# Charger_Interface_-_J1772_Interface.net
KiCad netlist of a schematic drawn in Altium Designer
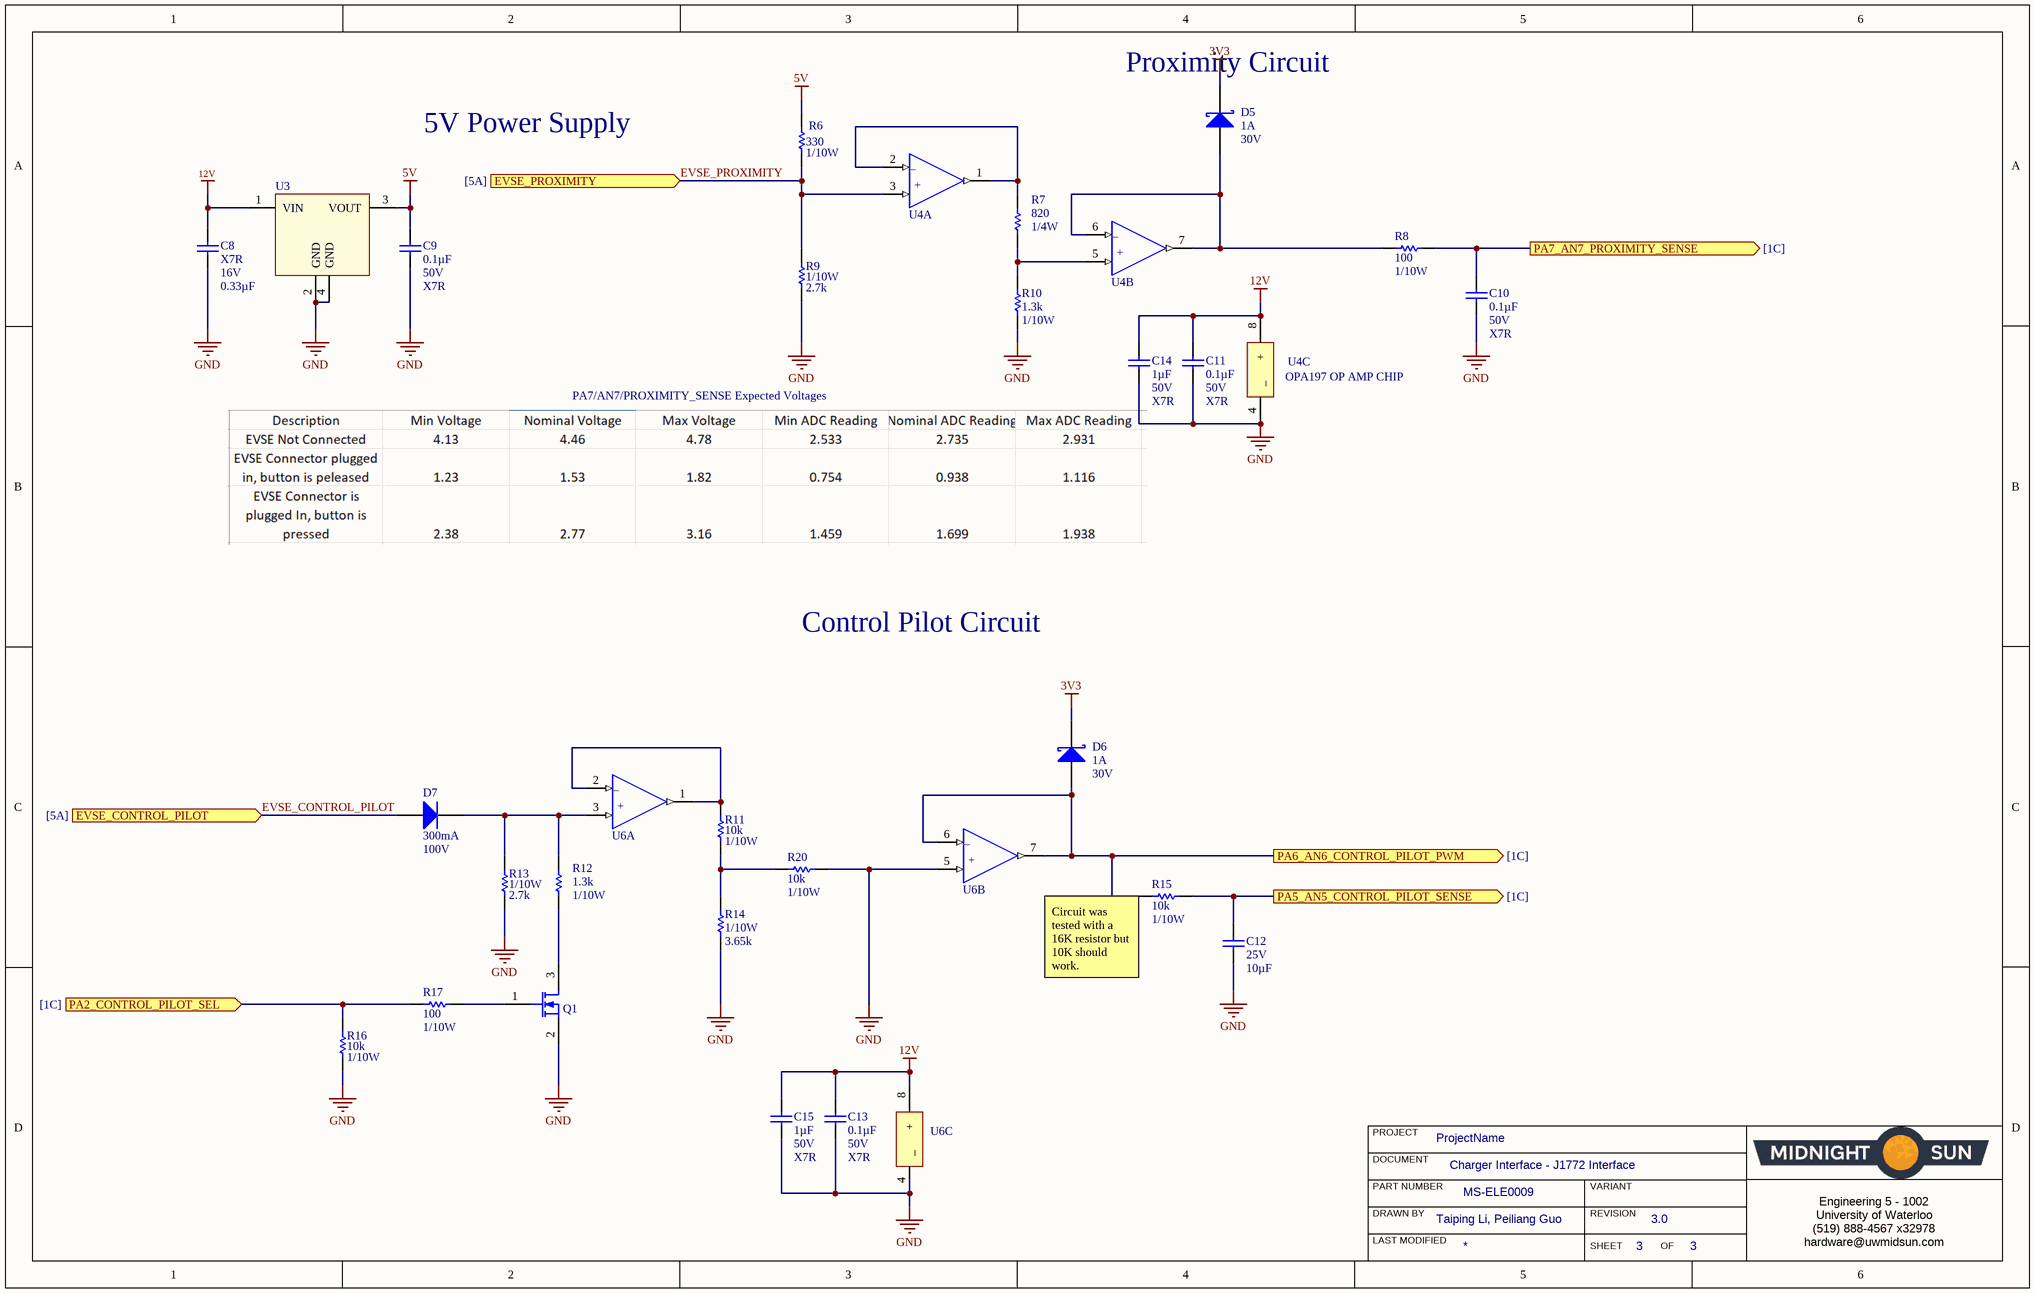
[diagram p0: Charger Interface - J1772 Interface.SchDoc]

(export (version "E")
  (design (tool "Eeschema 10.0.6"))
  (components
    (comp (ref "C8")
      (value "CAP CER 0.33UF 16V 10% X7R 0603")
      (footprint "CAP, 0603")
      (description "0.33µF ±10% 16V Ceramic Capacitor X7R 0603 (1608 Metric)")
      (fields
        (field (name "MANUFACTURER") "KEMET")
        (field (name "MANUFACTURER PART NUMBER") "C0603C334K4RACTU")
        (field (name "DIELECTRIC") "X7R")
        (field (name "VOLTAGE") "16V")
        (field (name "CAPACITANCE") "0.33µF")
      )
      (libsource (lib "Schematic Diagrams") (part "CAP CER 0.33UF 16V 10% X7R 0603"))
    )
    (comp (ref "C9")
      (value "CAP CER 0.1UF 50V 10% X7R 0603")
      (footprint "CAP, 0603")
      (description "0.10µF ±10% 50V Ceramic Capacitor X7R 0603 (1608 Metric)")
      (fields
        (field (name "TOLERANCE") "±10%")
        (field (name "CAPACITANCE") "0.1µF")
        (field (name "VOLTAGE") "50V")
        (field (name "TEMPERATURE COEFFICIENT") "X7R")
      )
      (libsource (lib "Schematic Diagrams") (part "CAP CER 0.1UF 50V 10% X7R 0603"))
    )
    (comp (ref "C10")
      (value "CAP CER 0.1UF 50V 10% X7R 0603")
      (footprint "CAP, 0603")
      (description "0.10µF ±10% 50V Ceramic Capacitor X7R 0603 (1608 Metric)")
      (fields
        (field (name "TOLERANCE") "±10%")
        (field (name "CAPACITANCE") "0.1µF")
        (field (name "VOLTAGE") "50V")
        (field (name "TEMPERATURE COEFFICIENT") "X7R")
      )
      (libsource (lib "Schematic Diagrams") (part "CAP CER 0.1UF 50V 10% X7R 0603"))
    )
    (comp (ref "C11")
      (value "CAP CER 0.1UF 50V 10% X7R 0603")
      (footprint "CAP, 0603")
      (description "0.10µF ±10% 50V Ceramic Capacitor X7R 0603 (1608 Metric)")
      (fields
        (field (name "TOLERANCE") "±10%")
        (field (name "CAPACITANCE") "0.1µF")
        (field (name "VOLTAGE") "50V")
        (field (name "TEMPERATURE COEFFICIENT") "X7R")
      )
      (libsource (lib "Schematic Diagrams") (part "CAP CER 0.1UF 50V 10% X7R 0603"))
    )
    (comp (ref "C12")
      (value "CAP CER 10uF 25V 10% X5R 0805")
      (footprint "CAP, 0805")
      (description "10µF ±10% 25V Ceramic Capacitor X5R 0805 (2012 Metric)")
      (fields
        (field (name "MANUFACTURER") "Murata Electronics North America")
        (field (name "MANUFACTURER PART NUMBER") "GRM21BR61E106KA73L")
        (field (name "VOLTAGE - RATED") "25V")
        (field (name "CAPACITANCE") "10µF")
      )
      (libsource (lib "Schematic Diagrams") (part "CAP CER 10uF 25V 10% X5R 0805"))
    )
    (comp (ref "C13")
      (value "CAP CER 0.1UF 50V 10% X7R 0603")
      (footprint "CAP, 0603")
      (description "0.10µF ±10% 50V Ceramic Capacitor X7R 0603 (1608 Metric)")
      (fields
        (field (name "TOLERANCE") "±10%")
        (field (name "CAPACITANCE") "0.1µF")
        (field (name "VOLTAGE") "50V")
        (field (name "TEMPERATURE COEFFICIENT") "X7R")
      )
      (libsource (lib "Schematic Diagrams") (part "CAP CER 0.1UF 50V 10% X7R 0603"))
    )
    (comp (ref "C14")
      (value "CAP CER 1UF 50V 10% X7R 0603")
      (footprint "CAP, 0603")
      (description "1µF ±10% 50V Ceramic Capacitor X7R 0603 (1608 Metric)")
      (fields
        (field (name "TOLERANCE") "±10%")
        (field (name "CAPACITANCE") "1µF")
        (field (name "VOLTAGE") "50V")
        (field (name "TEMPERATURE COEFFICIENT") "X7R")
      )
      (libsource (lib "Schematic Diagrams") (part "CAP CER 1UF 50V 10% X7R 0603"))
    )
    (comp (ref "C15")
      (value "CAP CER 1UF 50V 10% X7R 0603")
      (footprint "CAP, 0603")
      (description "1µF ±10% 50V Ceramic Capacitor X7R 0603 (1608 Metric)")
      (fields
        (field (name "TOLERANCE") "±10%")
        (field (name "CAPACITANCE") "1µF")
        (field (name "VOLTAGE") "50V")
        (field (name "TEMPERATURE COEFFICIENT") "X7R")
      )
      (libsource (lib "Schematic Diagrams") (part "CAP CER 1UF 50V 10% X7R 0603"))
    )
    (comp (ref "D5")
      (value "DIODE SCHOTTKY 30V 1A POWERDI123")
      (footprint "DIODE SCHOTTKY 30V 1A POWERDI123")
      (description "Diode Schottky 30V 1A Surface Mount PowerDI™ 123")
      (fields
        (field (name "MANUFACTURER") "Diodes Incorporated")
        (field (name "MANUFACTURER PART NUMBER") "DFLS130L-7")
        (field (name "CURRENT - AVERAGE RECTIFIED (IO)") "1A")
        (field (name "VOLTAGE - DC REVERSE (VR) (MAX)") "30V")
      )
      (libsource (lib "Schematic Diagrams") (part "DIODE SCHOTTKY 30V 1A POWERDI123"))
    )
    (comp (ref "D6")
      (value "DIODE SCHOTTKY 30V 1A POWERDI123")
      (footprint "DIODE SCHOTTKY 30V 1A POWERDI123")
      (description "Diode Schottky 30V 1A Surface Mount PowerDI™ 123")
      (fields
        (field (name "MANUFACTURER") "Diodes Incorporated")
        (field (name "MANUFACTURER PART NUMBER") "DFLS130L-7")
        (field (name "CURRENT - AVERAGE RECTIFIED (IO)") "1A")
        (field (name "VOLTAGE - DC REVERSE (VR) (MAX)") "30V")
      )
      (libsource (lib "Schematic Diagrams") (part "DIODE SCHOTTKY 30V 1A POWERDI123"))
    )
    (comp (ref "D7")
      (value "DIODE GEN PURP 100V 300MA SOD123")
      (footprint "DIODE GEN PURP 100V 300MA SOD123")
      (description "Diode Standard 100V 300mA (DC) Surface Mount SOD-123")
      (fields
        (field (name "MANUFACTURER") "Diodes Zetex")
        (field (name "MANUFACTURER PART NUMBER") "1N4148WQ-7-F")
        (field (name "FORWARD CURRENT") "300mA")
        (field (name "MAX REPETITIVE REVERSE VOLTAGE (VRRM)") "100V")
      )
      (libsource (lib "Schematic Diagrams") (part "DIODE GEN PURP 100V 300MA SOD123"))
    )
    (comp (ref "Q1")
      (value "MOSFET N-CH 30V 6.2A 0.9W SOT-23")
      (footprint "MOSFET N-CH 30V 6.2A 0.9W SOT-23")
      (description "N-Channel 30V 6.2A (Ta) 900mW (Ta) Surface Mount SOT-23")
      (fields (field (name "MANUFACTURER") "Diodes") (field (name "MANUFACTURER PART NUMBER") "DMN3023L-7"))
      (libsource (lib "Schematic Diagrams") (part "MOSFET N-CH 30V 6.2A 0.9W SOT-23"))
    )
    (comp (ref "R6")
      (value "RES 330 OHM 1% 1/10W 0603")
      (footprint "RES, 0603")
      (fields
        (field (name "MANUFACTURER") "TE Connectivity")
        (field (name "MANUFACTURER PART NUMBER") "1-2176339-9")
        (field (name "RESISTANCE") "330")
        (field (name "POWER") "1/10W")
      )
      (libsource (lib "Schematic Diagrams") (part "RES 330 OHM 1% 1/10W 0603"))
    )
    (comp (ref "R7")
      (value "RES 820 OHM 5% 1/4W 0603")
      (footprint "RES, 0603")
      (description "RES SMD 820 OHM 5% 1/4W 0603")
      (fields
        (field (name "TOLERANCE") "±5%")
        (field (name "RESISTANCE") "820")
        (field (name "POWER") "1/4W")
      )
      (libsource (lib "Schematic Diagrams") (part "RES 820 OHM 5% 1/4W 0603"))
    )
    (comp (ref "R8")
      (value "RES 100 OHM 1% 1/10W 0603")
      (footprint "RES, 0603")
      (description "100 Ohm ±1% 0.1W, 1/10W Chip Resistor 0603 (1608 Metric) Moisture Resistant Thick Film")
      (fields
        (field (name "TOLERANCE") "±1%")
        (field (name "RESISTANCE") "100")
        (field (name "POWER") "1/10W")
      )
      (libsource (lib "Schematic Diagrams") (part "RES 100 OHM 1% 1/10W 0603"))
    )
    (comp (ref "R9")
      (value "RES 2.7K OHM 1% 1/10W 0603")
      (footprint "RES, 0603")
      (fields
        (field (name "MANUFACTURER") "TE Connectivity")
        (field (name "MANUFACTURER PART NUMBER") "3-2176339-0")
        (field (name "POWER") "1/10W")
        (field (name "RESISTANCE") "2.7k")
      )
      (libsource (lib "Schematic Diagrams") (part "RES 2.7K OHM 1% 1/10W 0603"))
    )
    (comp (ref "R10")
      (value "RES 1.3K OHM 1% 1/10W 0603")
      (footprint "RES, 0603")
      (description "1.3 kOhms ±1% 0.1W, 1/10W Chip Resistor 0603 (1608 Metric) Moisture Resistant Thick Film")
      (fields
        (field (name "MANUFACTURER") "Yageo")
        (field (name "MANUFACTURER PART NUMBER") "RC0603FR-071K3L")
        (field (name "RESISTANCE") "1.3k")
        (field (name "POWER RATING") "1/10W")
      )
      (libsource (lib "Schematic Diagrams") (part "RES 1.3K OHM 1% 1/10W 0603"))
    )
    (comp (ref "R11")
      (value "RES 10K OHM 1% 1/10W 0603")
      (footprint "RES, 0603")
      (description "RES SMD 10K OHM 1% 1/10W 0603")
      (fields
        (field (name "TOLERANCE") "±1%")
        (field (name "RESISTANCE") "10k")
        (field (name "POWER") "1/10W")
      )
      (libsource (lib "Schematic Diagrams") (part "RES 10K OHM 1% 1/10W 0603"))
    )
    (comp (ref "R12")
      (value "RES 1.3K OHM 1% 1/10W 0603")
      (footprint "RES, 0603")
      (description "1.3 kOhms ±1% 0.1W, 1/10W Chip Resistor 0603 (1608 Metric) Moisture Resistant Thick Film")
      (fields
        (field (name "MANUFACTURER") "Yageo")
        (field (name "MANUFACTURER PART NUMBER") "RC0603FR-071K3L")
        (field (name "RESISTANCE") "1.3k")
        (field (name "POWER RATING") "1/10W")
      )
      (libsource (lib "Schematic Diagrams") (part "RES 1.3K OHM 1% 1/10W 0603"))
    )
    (comp (ref "R13")
      (value "RES 2.7K OHM 1% 1/10W 0603")
      (footprint "RES, 0603")
      (fields
        (field (name "MANUFACTURER") "TE Connectivity")
        (field (name "MANUFACTURER PART NUMBER") "3-2176339-0")
        (field (name "POWER") "1/10W")
        (field (name "RESISTANCE") "2.7k")
      )
      (libsource (lib "Schematic Diagrams") (part "RES 2.7K OHM 1% 1/10W 0603"))
    )
    (comp (ref "R14")
      (value "RES 3.65K OHM 0.1% 1/10W 0603")
      (footprint "RES, 0603")
      (description "3.65 kOhms ±0.1% 0.1W, 1/10W Chip Resistor 0603 (1608 Metric) Automotive AEC-Q200 Thin Film")
      (fields
        (field (name "MANUFACTURER") "Panasonic")
        (field (name "MANUFACTURER PART NUMBER") "ERA3AEB3651V")
        (field (name "POWER RATING") "1/10W")
        (field (name "RESISTANCE") "3.65k")
      )
      (libsource (lib "Schematic Diagrams") (part "RES 3.65K OHM 0.1% 1/10W 0603"))
    )
    (comp (ref "R15")
      (value "RES 10K OHM 1% 1/10W 0603")
      (footprint "RES, 0603")
      (description "RES SMD 10K OHM 1% 1/10W 0603")
      (fields
        (field (name "TOLERANCE") "±1%")
        (field (name "RESISTANCE") "10k")
        (field (name "POWER") "1/10W")
      )
      (libsource (lib "Schematic Diagrams") (part "RES 10K OHM 1% 1/10W 0603"))
    )
    (comp (ref "R16")
      (value "RES 10K OHM 1% 1/10W 0603")
      (footprint "RES, 0603")
      (description "RES SMD 10K OHM 1% 1/10W 0603")
      (fields
        (field (name "TOLERANCE") "±1%")
        (field (name "RESISTANCE") "10k")
        (field (name "POWER") "1/10W")
      )
      (libsource (lib "Schematic Diagrams") (part "RES 10K OHM 1% 1/10W 0603"))
    )
    (comp (ref "R17")
      (value "RES 100 OHM 1% 1/10W 0603")
      (footprint "RES, 0603")
      (description "100 Ohm ±1% 0.1W, 1/10W Chip Resistor 0603 (1608 Metric) Moisture Resistant Thick Film")
      (fields
        (field (name "TOLERANCE") "±1%")
        (field (name "RESISTANCE") "100")
        (field (name "POWER") "1/10W")
      )
      (libsource (lib "Schematic Diagrams") (part "RES 100 OHM 1% 1/10W 0603"))
    )
    (comp (ref "R20")
      (value "RES 10K OHM 1% 1/10W 0603")
      (footprint "RES, 0603")
      (description "RES SMD 10K OHM 1% 1/10W 0603")
      (fields
        (field (name "TOLERANCE") "±1%")
        (field (name "RESISTANCE") "10k")
        (field (name "POWER") "1/10W")
      )
      (libsource (lib "Schematic Diagrams") (part "RES 10K OHM 1% 1/10W 0603"))
    )
    (comp (ref "U3")
      (value "IC REG LDO 5V 0.5A SOT223")
      (footprint "SOT223_N")
      (description "Linear Voltage Regulator IC Positive Fixed Output 5V 500mA SOT-223-4")
      (libsource (lib "Schematic Diagrams") (part "IC REG LDO 5V 0.5A SOT223"))
    )
    (comp (ref "U4")
      (value "IC OP AMP DUAL GP RR 10MHZ 8-VSSOP")
      (footprint "IC DUAL OPAMP OPA2197 8-VSSOP")
      (description "General Purpose Amplifier 2 Circuit Rail-to-Rail 8-VSSOP")
      (fields
        (field (name "MANUFACTURER") "Texas Instruments")
        (field (name "MANUFACTURER PART NUMBER") "OPA2197IDGKR")
      )
      (libsource (lib "Schematic Diagrams") (part "IC OP AMP DUAL GP RR 10MHZ 8-VSSOP"))
    )
    (comp (ref "U6")
      (value "IC OP AMP DUAL GP RR 10MHZ 8-VSSOP")
      (footprint "IC DUAL OPAMP OPA2197 8-VSSOP")
      (description "General Purpose Amplifier 2 Circuit Rail-to-Rail 8-VSSOP")
      (fields
        (field (name "MANUFACTURER") "Texas Instruments")
        (field (name "MANUFACTURER PART NUMBER") "OPA2197IDGKR")
      )
      (libsource (lib "") (part "IC OP AMP DUAL GP RR 10MHZ 8-VSSOP_1"))
    )
  )
  (nets
    (net (code "1") (name "/EVSE_CONTROL_PILOT") (class "Default")
      (node (ref "D7") (pin "1") (pinfunction "A_1") (pintype "passive"))
    )
    (net (code "2") (name "/EVSE_PROXIMITY") (class "Default")
      (node (ref "R6") (pin "2") (pinfunction "2_2") (pintype "passive"))
      (node (ref "R9") (pin "1") (pinfunction "1_1") (pintype "passive"))
      (node (ref "U4") (pin "3") (pinfunction "+IN_A_3") (pintype "input"))
    )
    (net (code "3") (name "/PA2_CONTROL_PILOT_SEL") (class "Default")
      (node (ref "R16") (pin "1") (pinfunction "1_1") (pintype "passive"))
      (node (ref "R17") (pin "1") (pinfunction "1_1") (pintype "passive"))
    )
    (net (code "4") (name "/PA5_AN5_CONTROL_PILOT_SENSE") (class "Default")
      (node (ref "C12") (pin "1") (pinfunction "1_1") (pintype "passive"))
      (node (ref "R15") (pin "2") (pinfunction "2_2") (pintype "passive"))
    )
    (net (code "5") (name "/PA6_AN6_CONTROL_PILOT_PWM") (class "Default")
      (node (ref "D6") (pin "1") (pinfunction "A_1") (pintype "passive"))
      (node (ref "R15") (pin "1") (pinfunction "1_1") (pintype "passive"))
      (node (ref "U6") (pin "6") (pinfunction "-IN_B_6") (pintype "input"))
      (node (ref "U6") (pin "7") (pinfunction "OUT_B_7") (pintype "output"))
    )
    (net (code "6") (name "/PA7_AN7_PROXIMITY_SENSE") (class "Default")
      (node (ref "C10") (pin "1") (pinfunction "1_1") (pintype "passive"))
      (node (ref "R8") (pin "2") (pinfunction "2_2") (pintype "passive"))
    )
    (net (code "7") (name "3V3") (class "Default")
      (node (ref "D5") (pin "2") (pinfunction "K_2") (pintype "passive"))
      (node (ref "D6") (pin "2") (pinfunction "K_2") (pintype "passive"))
    )
    (net (code "8") (name "5V") (class "Default")
      (node (ref "C9") (pin "1") (pinfunction "1_1") (pintype "passive"))
      (node (ref "R6") (pin "1") (pinfunction "1_1") (pintype "passive"))
      (node (ref "U3") (pin "3") (pinfunction "VOUT_3") (pintype "power_in"))
    )
    (net (code "9") (name "12V") (class "Default")
      (node (ref "C11") (pin "1") (pinfunction "1_1") (pintype "passive"))
      (node (ref "C13") (pin "1") (pinfunction "1_1") (pintype "passive"))
      (node (ref "C14") (pin "1") (pinfunction "1_1") (pintype "passive"))
      (node (ref "C15") (pin "1") (pinfunction "1_1") (pintype "passive"))
      (node (ref "C8") (pin "1") (pinfunction "1_1") (pintype "passive"))
      (node (ref "U3") (pin "1") (pinfunction "VIN_1") (pintype "power_in"))
      (node (ref "U4") (pin "8") (pinfunction "+_8") (pintype "power_in"))
      (node (ref "U6") (pin "8") (pinfunction "+_8") (pintype "power_in"))
    )
    (net (code "10") (name "GND") (class "Default")
      (node (ref "C10") (pin "2") (pinfunction "2_2") (pintype "passive"))
      (node (ref "C11") (pin "2") (pinfunction "2_2") (pintype "passive"))
      (node (ref "C12") (pin "2") (pinfunction "2_2") (pintype "passive"))
      (node (ref "C13") (pin "2") (pinfunction "2_2") (pintype "passive"))
      (node (ref "C14") (pin "2") (pinfunction "2_2") (pintype "passive"))
      (node (ref "C15") (pin "2") (pinfunction "2_2") (pintype "passive"))
      (node (ref "C8") (pin "2") (pinfunction "2_2") (pintype "passive"))
      (node (ref "C9") (pin "2") (pinfunction "2_2") (pintype "passive"))
      (node (ref "Q1") (pin "2") (pinfunction "S_2") (pintype "passive"))
      (node (ref "R10") (pin "2") (pinfunction "2_2") (pintype "passive"))
      (node (ref "R13") (pin "2") (pinfunction "2_2") (pintype "passive"))
      (node (ref "R14") (pin "2") (pinfunction "2_2") (pintype "passive"))
      (node (ref "R16") (pin "2") (pinfunction "2_2") (pintype "passive"))
      (node (ref "R20") (pin "2") (pinfunction "2_2") (pintype "passive"))
      (node (ref "R9") (pin "2") (pinfunction "2_2") (pintype "passive"))
      (node (ref "U3") (pin "2") (pinfunction "GND_2") (pintype "power_in"))
      (node (ref "U3") (pin "4") (pinfunction "GND_4") (pintype "power_in"))
      (node (ref "U4") (pin "4") (pinfunction "__4") (pintype "power_in"))
      (node (ref "U6") (pin "4") (pinfunction "__4") (pintype "power_in"))
      (node (ref "U6") (pin "5") (pinfunction "+IN_B_5") (pintype "input"))
    )
    (net (code "11") (name "Net-(D5-A)") (class "Default")
      (node (ref "D5") (pin "1") (pinfunction "A_1") (pintype "passive"))
      (node (ref "R8") (pin "1") (pinfunction "1_1") (pintype "passive"))
      (node (ref "U4") (pin "6") (pinfunction "-IN_B_6") (pintype "input"))
      (node (ref "U4") (pin "7") (pinfunction "OUT_B_7") (pintype "output"))
    )
    (net (code "12") (name "Net-(D7-K)") (class "Default")
      (node (ref "D7") (pin "2") (pinfunction "K_2") (pintype "passive"))
      (node (ref "R12") (pin "1") (pinfunction "1_1") (pintype "passive"))
      (node (ref "R13") (pin "1") (pinfunction "1_1") (pintype "passive"))
      (node (ref "U6") (pin "3") (pinfunction "+IN_A_3") (pintype "input"))
    )
    (net (code "13") (name "Net-(Q1-D)") (class "Default")
      (node (ref "Q1") (pin "3") (pinfunction "D_3") (pintype "passive"))
      (node (ref "R12") (pin "2") (pinfunction "2_2") (pintype "passive"))
    )
    (net (code "14") (name "Net-(Q1-G)") (class "Default")
      (node (ref "Q1") (pin "1") (pinfunction "G_1") (pintype "passive"))
      (node (ref "R17") (pin "2") (pinfunction "2_2") (pintype "passive"))
    )
    (net (code "15") (name "Net-(R11-Pad2)") (class "Default")
      (node (ref "R11") (pin "2") (pinfunction "2_2") (pintype "passive"))
      (node (ref "R14") (pin "1") (pinfunction "1_1") (pintype "passive"))
      (node (ref "R20") (pin "1") (pinfunction "1_1") (pintype "passive"))
    )
    (net (code "16") (name "Net-(U4A--IN_A)") (class "Default")
      (node (ref "R7") (pin "1") (pinfunction "1_1") (pintype "passive"))
      (node (ref "U4") (pin "1") (pinfunction "OUT_A_1") (pintype "output"))
      (node (ref "U4") (pin "2") (pinfunction "-IN_A_2") (pintype "input"))
    )
    (net (code "17") (name "Net-(U4B-+IN_B)") (class "Default")
      (node (ref "R10") (pin "1") (pinfunction "1_1") (pintype "passive"))
      (node (ref "R7") (pin "2") (pinfunction "2_2") (pintype "passive"))
      (node (ref "U4") (pin "5") (pinfunction "+IN_B_5") (pintype "input"))
    )
    (net (code "18") (name "Net-(U6A--IN_A)") (class "Default")
      (node (ref "R11") (pin "1") (pinfunction "1_1") (pintype "passive"))
      (node (ref "U6") (pin "1") (pinfunction "OUT_A_1") (pintype "output"))
      (node (ref "U6") (pin "2") (pinfunction "-IN_A_2") (pintype "input"))
    )
  )
)
